# Schematic.net
KiCad netlist of a schematic drawn in EasyEDA
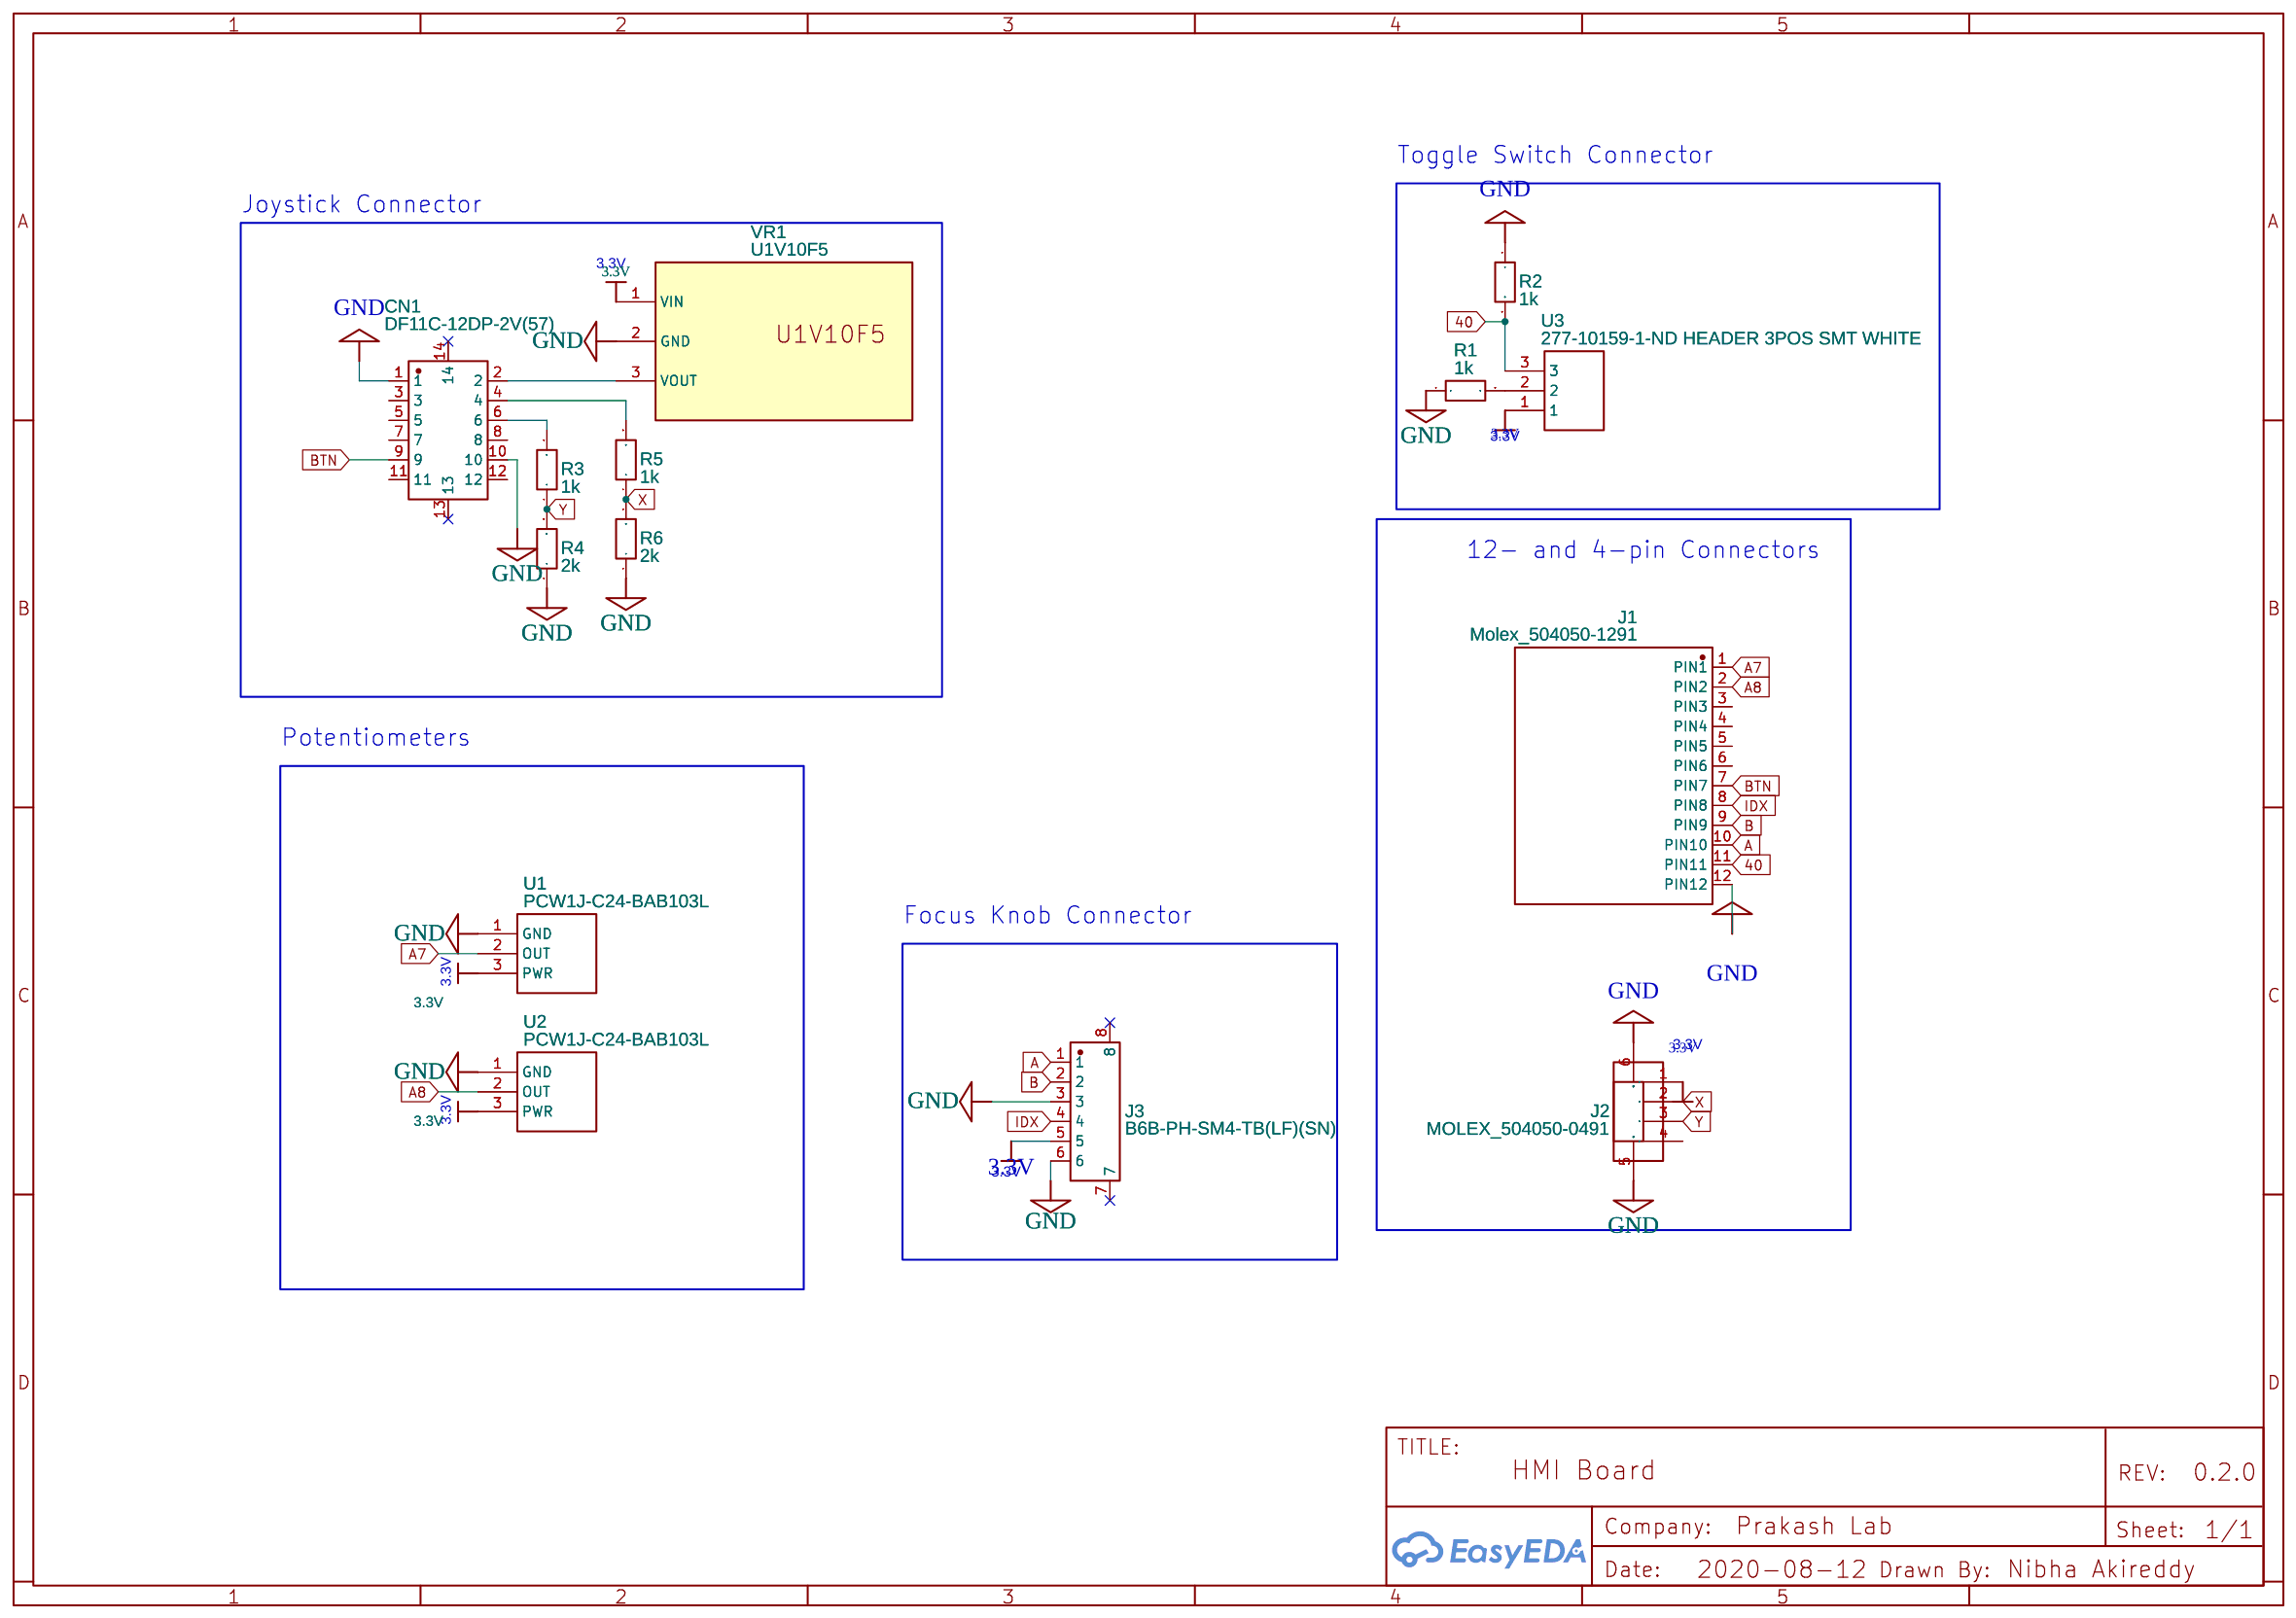
[diagram p0: schematic sheet]

(export (version "E")
  (design (tool "Eeschema 10.0.6"))
  (components
    (comp (ref "CN1")
      (value "DF11C-12DP-2V(57)")
      (fields (field (name "BOM_Supplier Part") "C597834"))
      (libsource (lib "") (part "DF11C-12DP-2V(57)"))
    )
    (comp (ref "J1")
      (value "Molex_504050-1291")
      (fields
        (field (name "BOM_Manufacturer Part") "504050-1291")
        (field (name "BOM_Supplier Part") "‎WM16219CT-ND")
      )
      (libsource (lib "") (part "Molex_504050-1291"))
    )
    (comp (ref "J2")
      (value "MOLEX_504050-0491")
      (fields
        (field (name "BOM_Manufacturer Part") "504050-0491")
        (field (name "BOM_Supplier Part") "789-8359")
      )
      (libsource (lib "") (part "MOLEX_504050-0491"))
    )
    (comp (ref "J3")
      (value "B6B-PH-SM4-TB(LF)(SN)")
      (fields (field (name "BOM_Supplier Part") "C471518"))
      (libsource (lib "") (part "B6B-PH-SM4-TB(LF)(SN)"))
    )
    (comp (ref "R1") (value "1k") (libsource (lib "") (part "R_1206_EU")))
    (comp (ref "R2") (value "1k") (libsource (lib "") (part "R_0201_EU")))
    (comp (ref "R3") (value "1k") (libsource (lib "") (part "R_0201_EU_1")))
    (comp (ref "R4") (value "2k") (libsource (lib "") (part "R_0201_EU_1")))
    (comp (ref "R5") (value "1k") (libsource (lib "") (part "R_0201_EU_1")))
    (comp (ref "R6") (value "2k") (libsource (lib "") (part "R_0201_EU_1")))
    (comp (ref "U1")
      (value "PCW1J-C24-BAB103L")
      (fields (field (name "BOM_Supplier Part") "PCW1J-C24-BAB103L-ND"))
      (libsource (lib "") (part "PCW1J-C24-BAB103L"))
    )
    (comp (ref "U2")
      (value "PCW1J-C24-BAB103L")
      (fields (field (name "BOM_Supplier Part") "PCW1J-C24-BAB103L-ND"))
      (libsource (lib "") (part "PCW1J-C24-BAB103L"))
    )
    (comp (ref "U3")
      (value "277-10159-1-ND HEADER 3POS SMT WHITE")
      (fields
        (field (name "BOM_Manufacturer Part") "1778706")
        (field (name "BOM_Supplier Part") "277-10159-1-ND")
      )
      (libsource (lib "") (part "277-10159-1-ND HEADER 3POS SMT WHITE"))
    )
    (comp (ref "VR1") (value "U1V10F5") (libsource (lib "") (part "U1V10F5")))
  )
  (nets
    (net (code "1") (name "3.3V") (class "Default")
      (node (ref "J2") (pin "1") (pinfunction "1_1") (pintype "bidirectional"))
      (node (ref "J3") (pin "5") (pinfunction "5_5") (pintype "unspecified"))
      (node (ref "U1") (pin "3") (pinfunction "PWR_3") (pintype "unspecified"))
      (node (ref "U2") (pin "3") (pinfunction "PWR_3") (pintype "unspecified"))
      (node (ref "U3") (pin "1") (pinfunction "1_1") (pintype "unspecified"))
      (node (ref "VR1") (pin "1") (pinfunction "VIN_1") (pintype "unspecified"))
    )
    (net (code "2") (name "40") (class "Default")
      (node (ref "J1") (pin "11") (pinfunction "PIN11_11") (pintype "unspecified"))
      (node (ref "R2") (pin "2") (pinfunction "2_2") (pintype "unspecified"))
      (node (ref "U3") (pin "3") (pinfunction "3_3") (pintype "unspecified"))
    )
    (net (code "3") (name "A") (class "Default")
      (node (ref "J1") (pin "10") (pinfunction "PIN10_10") (pintype "unspecified"))
      (node (ref "J3") (pin "1") (pinfunction "1_1") (pintype "unspecified"))
    )
    (net (code "4") (name "A7") (class "Default")
      (node (ref "J1") (pin "1") (pinfunction "PIN1_1") (pintype "unspecified"))
      (node (ref "U1") (pin "2") (pinfunction "OUT_2") (pintype "unspecified"))
    )
    (net (code "5") (name "A8") (class "Default")
      (node (ref "J1") (pin "2") (pinfunction "PIN2_2") (pintype "unspecified"))
      (node (ref "U2") (pin "2") (pinfunction "OUT_2") (pintype "unspecified"))
    )
    (net (code "6") (name "B") (class "Default")
      (node (ref "J1") (pin "9") (pinfunction "PIN9_9") (pintype "unspecified"))
      (node (ref "J3") (pin "2") (pinfunction "2_2") (pintype "unspecified"))
    )
    (net (code "7") (name "BTN") (class "Default")
      (node (ref "CN1") (pin "9") (pinfunction "9_9") (pintype "unspecified"))
      (node (ref "J1") (pin "7") (pinfunction "PIN7_7") (pintype "unspecified"))
    )
    (net (code "8") (name "GND") (class "Default")
      (node (ref "CN1") (pin "1") (pinfunction "1_1") (pintype "unspecified"))
      (node (ref "CN1") (pin "10") (pinfunction "10_10") (pintype "unspecified"))
      (node (ref "J1") (pin "12") (pinfunction "PIN12_12") (pintype "unspecified"))
      (node (ref "J2") (pin "5") (pinfunction "MNT_1_5") (pintype "bidirectional"))
      (node (ref "J2") (pin "6") (pinfunction "MNT_2_6") (pintype "bidirectional"))
      (node (ref "J3") (pin "3") (pinfunction "3_3") (pintype "unspecified"))
      (node (ref "J3") (pin "6") (pinfunction "6_6") (pintype "unspecified"))
      (node (ref "R1") (pin "1") (pinfunction "1_1") (pintype "unspecified"))
      (node (ref "R2") (pin "1") (pinfunction "1_1") (pintype "unspecified"))
      (node (ref "R4") (pin "1") (pinfunction "1_1") (pintype "unspecified"))
      (node (ref "R6") (pin "1") (pinfunction "1_1") (pintype "unspecified"))
      (node (ref "U1") (pin "1") (pinfunction "GND_1") (pintype "unspecified"))
      (node (ref "U2") (pin "1") (pinfunction "GND_1") (pintype "unspecified"))
      (node (ref "VR1") (pin "2") (pinfunction "GND_2") (pintype "unspecified"))
    )
    (net (code "9") (name "IDX") (class "Default")
      (node (ref "J1") (pin "8") (pinfunction "PIN8_8") (pintype "unspecified"))
      (node (ref "J3") (pin "4") (pinfunction "4_4") (pintype "unspecified"))
    )
    (net (code "10") (name "Net-(CN1-Pad4)") (class "Default")
      (node (ref "CN1") (pin "4") (pinfunction "4_4") (pintype "unspecified"))
      (node (ref "R5") (pin "2") (pinfunction "2_2") (pintype "unspecified"))
    )
    (net (code "11") (name "Net-(CN1-Pad6)") (class "Default")
      (node (ref "CN1") (pin "6") (pinfunction "6_6") (pintype "unspecified"))
      (node (ref "R3") (pin "2") (pinfunction "2_2") (pintype "unspecified"))
    )
    (net (code "12") (name "Net-(R1-Pad2)") (class "Default")
      (node (ref "R1") (pin "2") (pinfunction "2_2") (pintype "unspecified"))
      (node (ref "U3") (pin "2") (pinfunction "2_2") (pintype "unspecified"))
    )
    (net (code "13") (name "Net-(VR1-VOUT)") (class "Default")
      (node (ref "CN1") (pin "2") (pinfunction "2_2") (pintype "unspecified"))
      (node (ref "VR1") (pin "3") (pinfunction "VOUT_3") (pintype "unspecified"))
    )
    (net (code "14") (name "X") (class "Default")
      (node (ref "J2") (pin "2") (pinfunction "2_2") (pintype "bidirectional"))
      (node (ref "R5") (pin "1") (pinfunction "1_1") (pintype "unspecified"))
      (node (ref "R6") (pin "2") (pinfunction "2_2") (pintype "unspecified"))
    )
    (net (code "15") (name "Y") (class "Default")
      (node (ref "J2") (pin "3") (pinfunction "3_3") (pintype "bidirectional"))
      (node (ref "R3") (pin "1") (pinfunction "1_1") (pintype "unspecified"))
      (node (ref "R4") (pin "2") (pinfunction "2_2") (pintype "unspecified"))
    )
    (net (code "16") (name "unconnected-(CN1-Pad3)") (class "Default")
      (node (ref "CN1") (pin "3") (pinfunction "3_3") (pintype "unspecified"))
    )
    (net (code "17") (name "unconnected-(CN1-Pad5)") (class "Default")
      (node (ref "CN1") (pin "5") (pinfunction "5_5") (pintype "unspecified"))
    )
    (net (code "18") (name "unconnected-(CN1-Pad7)") (class "Default")
      (node (ref "CN1") (pin "7") (pinfunction "7_7") (pintype "unspecified"))
    )
    (net (code "19") (name "unconnected-(CN1-Pad8)") (class "Default")
      (node (ref "CN1") (pin "8") (pinfunction "8_8") (pintype "unspecified"))
    )
    (net (code "20") (name "unconnected-(CN1-Pad11)") (class "Default")
      (node (ref "CN1") (pin "11") (pinfunction "11_11") (pintype "unspecified"))
    )
    (net (code "21") (name "unconnected-(CN1-Pad12)") (class "Default")
      (node (ref "CN1") (pin "12") (pinfunction "12_12") (pintype "unspecified"))
    )
    (net (code "22") (name "unconnected-(CN1-Pad13)") (class "Default")
      (node (ref "CN1") (pin "13") (pinfunction "13_13") (pintype "unspecified+no_connect"))
    )
    (net (code "23") (name "unconnected-(CN1-Pad14)") (class "Default")
      (node (ref "CN1") (pin "14") (pinfunction "14_14") (pintype "unspecified+no_connect"))
    )
    (net (code "24") (name "unconnected-(J1-PIN3-Pad3)") (class "Default")
      (node (ref "J1") (pin "3") (pinfunction "PIN3_3") (pintype "unspecified"))
    )
    (net (code "25") (name "unconnected-(J1-PIN4-Pad4)") (class "Default")
      (node (ref "J1") (pin "4") (pinfunction "PIN4_4") (pintype "unspecified"))
    )
    (net (code "26") (name "unconnected-(J1-PIN5-Pad5)") (class "Default")
      (node (ref "J1") (pin "5") (pinfunction "PIN5_5") (pintype "unspecified"))
    )
    (net (code "27") (name "unconnected-(J1-PIN6-Pad6)") (class "Default")
      (node (ref "J1") (pin "6") (pinfunction "PIN6_6") (pintype "unspecified"))
    )
    (net (code "28") (name "unconnected-(J2-Pad4)") (class "Default")
      (node (ref "J2") (pin "4") (pinfunction "4_4") (pintype "bidirectional"))
    )
    (net (code "29") (name "unconnected-(J3-Pad7)") (class "Default")
      (node (ref "J3") (pin "7") (pinfunction "7_7") (pintype "unspecified+no_connect"))
    )
    (net (code "30") (name "unconnected-(J3-Pad8)") (class "Default")
      (node (ref "J3") (pin "8") (pinfunction "8_8") (pintype "unspecified+no_connect"))
    )
  )
)
